# dual-verter.net
KiCad netlist of a schematic drawn in EAGLE
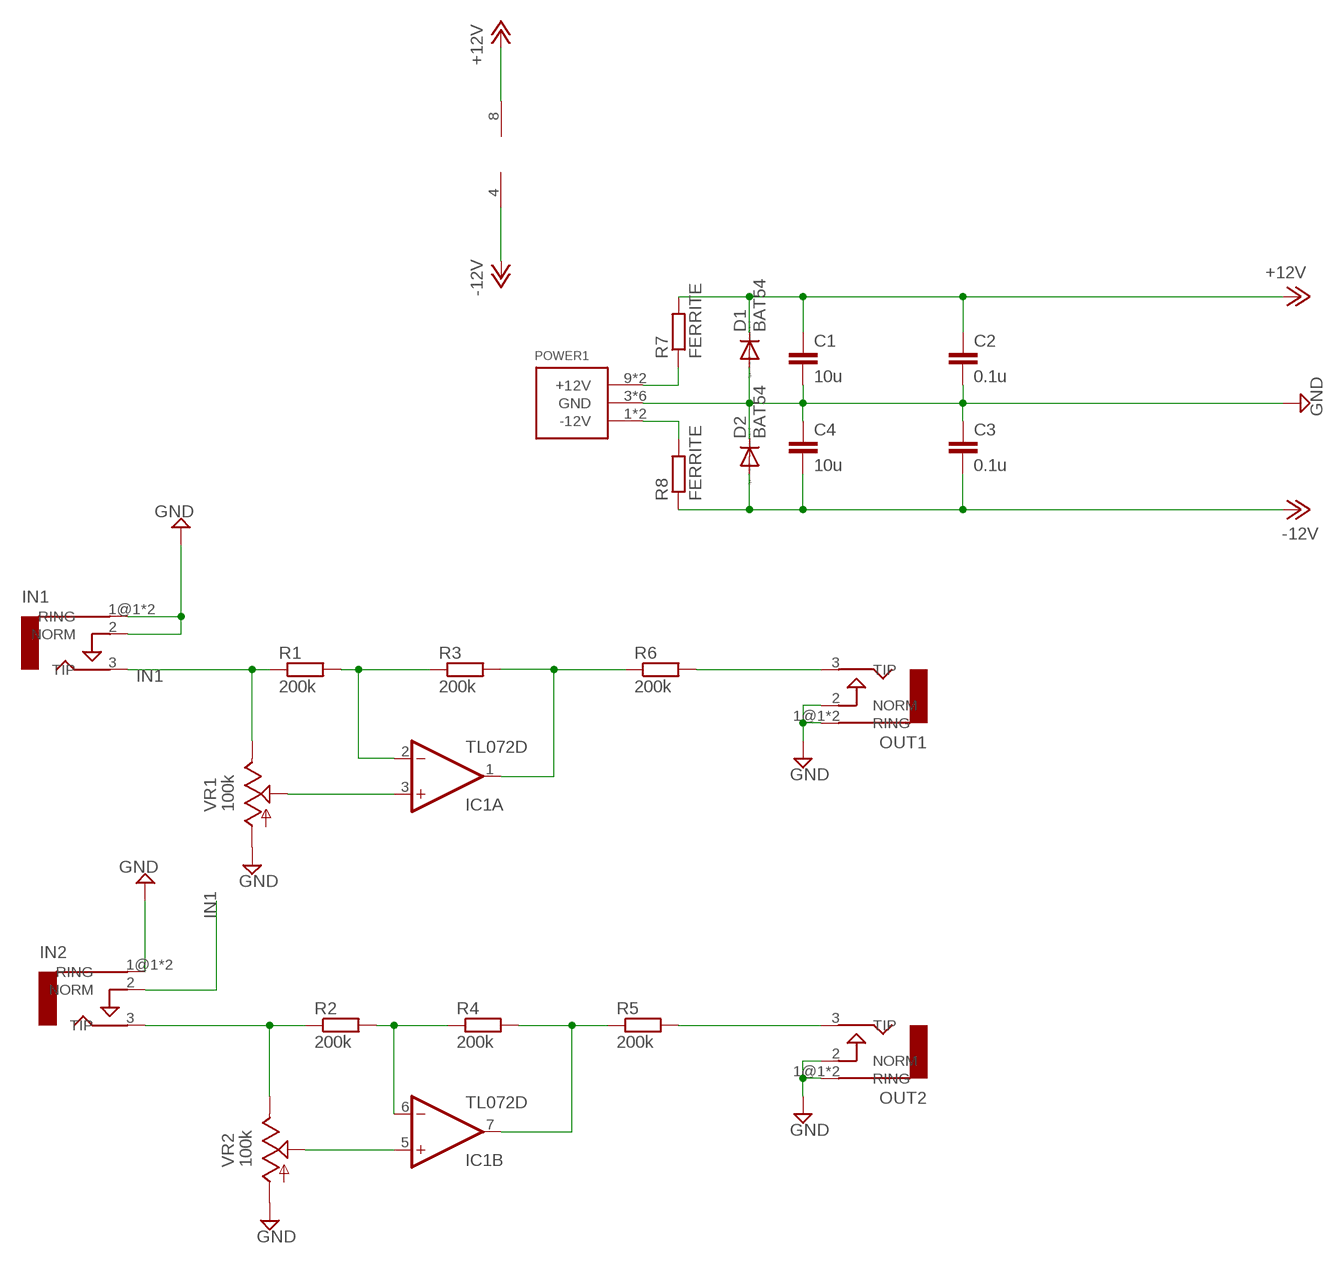
[diagram p0: schematic, sheet 1]

(export (version "E")
  (design (tool "Eeschema 10.0.6"))
  (components
    (comp (ref "C1")
      (value "10u")
      (footprint "eagle-import:C0805")
      (libsource (lib "eagle-import") (part "C-EUC0805"))
    )
    (comp (ref "C2")
      (value "0.1u")
      (footprint "eagle-import:C0805")
      (libsource (lib "eagle-import") (part "C-EUC0805"))
    )
    (comp (ref "C3")
      (value "0.1u")
      (footprint "eagle-import:C0805")
      (libsource (lib "eagle-import") (part "C-EUC0805"))
    )
    (comp (ref "C4")
      (value "10u")
      (footprint "eagle-import:C0805")
      (libsource (lib "eagle-import") (part "C-EUC0805"))
    )
    (comp (ref "D1")
      (value "BAT54")
      (footprint "eagle-import:SOD323-W")
      (libsource (lib "eagle-import") (part "DIODE-SOD323-W"))
    )
    (comp (ref "D2")
      (value "BAT54")
      (footprint "eagle-import:SOD323-W")
      (libsource (lib "eagle-import") (part "DIODE-SOD323-W"))
    )
    (comp (ref "IC1")
      (value "TL072D")
      (footprint "eagle-import:SO08")
      (libsource (lib "eagle-import") (part "TL072D"))
    )
    (comp (ref "IN1")
      (value "AUDIO-JACKERTHENVAR")
      (footprint "eagle-import:ERTHENVAR-JACK")
      (libsource (lib "eagle-import") (part "AUDIO-JACKERTHENVAR"))
    )
    (comp (ref "IN2")
      (value "AUDIO-JACKERTHENVAR")
      (footprint "eagle-import:ERTHENVAR-JACK")
      (libsource (lib "eagle-import") (part "AUDIO-JACKERTHENVAR"))
    )
    (comp (ref "OUT1")
      (value "AUDIO-JACKERTHENVAR")
      (footprint "eagle-import:ERTHENVAR-JACK")
      (libsource (lib "eagle-import") (part "AUDIO-JACKERTHENVAR"))
    )
    (comp (ref "OUT2")
      (value "AUDIO-JACKERTHENVAR")
      (footprint "eagle-import:ERTHENVAR-JACK")
      (libsource (lib "eagle-import") (part "AUDIO-JACKERTHENVAR"))
    )
    (comp (ref "POWER1")
      (value "POWER_SIMPLE10")
      (footprint "eagle-import:POWER_10")
      (libsource (lib "eagle-import") (part "POWER_SIMPLE10"))
    )
    (comp (ref "R1")
      (value "200k")
      (footprint "eagle-import:R0805")
      (libsource (lib "eagle-import") (part "R-EU_R0805"))
    )
    (comp (ref "R2")
      (value "200k")
      (footprint "eagle-import:R0805")
      (libsource (lib "eagle-import") (part "R-EU_R0805"))
    )
    (comp (ref "R3")
      (value "200k")
      (footprint "eagle-import:R0805")
      (libsource (lib "eagle-import") (part "R-EU_R0805"))
    )
    (comp (ref "R4")
      (value "200k")
      (footprint "eagle-import:R0805")
      (libsource (lib "eagle-import") (part "R-EU_R0805"))
    )
    (comp (ref "R5")
      (value "200k")
      (footprint "eagle-import:R0805")
      (libsource (lib "eagle-import") (part "R-EU_R0805"))
    )
    (comp (ref "R6")
      (value "200k")
      (footprint "eagle-import:R0805")
      (libsource (lib "eagle-import") (part "R-EU_R0805"))
    )
    (comp (ref "R7")
      (value "FERRITE")
      (footprint "eagle-import:R0805")
      (libsource (lib "eagle-import") (part "R-EU_R0805"))
    )
    (comp (ref "R8")
      (value "FERRITE")
      (footprint "eagle-import:R0805")
      (libsource (lib "eagle-import") (part "R-EU_R0805"))
    )
    (comp (ref "VR1")
      (value "100k")
      (footprint "eagle-import:9MM_SNAP-IN_POT")
      (libsource (lib "eagle-import") (part "9MM_SNAP-IN_POT_"))
    )
    (comp (ref "VR2")
      (value "100k")
      (footprint "eagle-import:9MM_SNAP-IN_POT")
      (libsource (lib "eagle-import") (part "9MM_SNAP-IN_POT_"))
    )
  )
  (nets
    (net (code "1") (name "+12V") (class "Default")
      (node (ref "C1") (pin "1") (pinfunction "1_1") (pintype "passive"))
      (node (ref "C2") (pin "1") (pinfunction "1_1") (pintype "passive"))
      (node (ref "D1") (pin "C") (pinfunction "C_C") (pintype "passive"))
      (node (ref "IC1") (pin "8") (pinfunction "V+_8") (pintype "power_in"))
      (node (ref "R7") (pin "2") (pinfunction "2_2") (pintype "passive"))
    )
    (net (code "2") (name "-12V") (class "Default")
      (node (ref "C3") (pin "2") (pinfunction "2_2") (pintype "passive"))
      (node (ref "C4") (pin "2") (pinfunction "2_2") (pintype "passive"))
      (node (ref "D2") (pin "A") (pinfunction "A_A") (pintype "passive"))
      (node (ref "IC1") (pin "4") (pinfunction "V-_4") (pintype "power_in"))
      (node (ref "R8") (pin "1") (pinfunction "1_1") (pintype "passive"))
    )
    (net (code "3") (name "/IN1") (class "Default")
      (node (ref "IN1") (pin "3") (pinfunction "TIP_3") (pintype "bidirectional"))
      (node (ref "IN2") (pin "2") (pinfunction "NORM_2") (pintype "bidirectional"))
      (node (ref "R1") (pin "1") (pinfunction "1_1") (pintype "passive"))
      (node (ref "VR1") (pin "3") (pinfunction "E_3") (pintype "passive"))
    )
    (net (code "4") (name "GND") (class "Default")
      (node (ref "C1") (pin "2") (pinfunction "2_2") (pintype "passive"))
      (node (ref "C2") (pin "2") (pinfunction "2_2") (pintype "passive"))
      (node (ref "C3") (pin "1") (pinfunction "1_1") (pintype "passive"))
      (node (ref "C4") (pin "1") (pinfunction "1_1") (pintype "passive"))
      (node (ref "D1") (pin "A") (pinfunction "A_A") (pintype "passive"))
      (node (ref "D2") (pin "C") (pinfunction "C_C") (pintype "passive"))
      (node (ref "IN1") (pin "1@1") (pinfunction "RING_1@1") (pintype "bidirectional"))
      (node (ref "IN1") (pin "1@2") (pinfunction "RING_1@2") (pintype "bidirectional"))
      (node (ref "IN1") (pin "2") (pinfunction "NORM_2") (pintype "bidirectional"))
      (node (ref "IN2") (pin "1@1") (pinfunction "RING_1@1") (pintype "bidirectional"))
      (node (ref "IN2") (pin "1@2") (pinfunction "RING_1@2") (pintype "bidirectional"))
      (node (ref "OUT1") (pin "1@1") (pinfunction "RING_1@1") (pintype "bidirectional"))
      (node (ref "OUT1") (pin "1@2") (pinfunction "RING_1@2") (pintype "bidirectional"))
      (node (ref "OUT1") (pin "2") (pinfunction "NORM_2") (pintype "bidirectional"))
      (node (ref "OUT2") (pin "1@1") (pinfunction "RING_1@1") (pintype "bidirectional"))
      (node (ref "OUT2") (pin "1@2") (pinfunction "RING_1@2") (pintype "bidirectional"))
      (node (ref "OUT2") (pin "2") (pinfunction "NORM_2") (pintype "bidirectional"))
      (node (ref "POWER1") (pin "3") (pinfunction "GND_3") (pintype "bidirectional"))
      (node (ref "POWER1") (pin "4") (pinfunction "GND_4") (pintype "bidirectional"))
      (node (ref "POWER1") (pin "5") (pinfunction "GND_5") (pintype "bidirectional"))
      (node (ref "POWER1") (pin "6") (pinfunction "GND_6") (pintype "bidirectional"))
      (node (ref "POWER1") (pin "7") (pinfunction "GND_7") (pintype "bidirectional"))
      (node (ref "POWER1") (pin "8") (pinfunction "GND_8") (pintype "bidirectional"))
      (node (ref "VR1") (pin "1") (pinfunction "A_1") (pintype "passive"))
      (node (ref "VR2") (pin "1") (pinfunction "A_1") (pintype "passive"))
    )
    (net (code "5") (name "Net-(IC1A-+IN)") (class "Default")
      (node (ref "IC1") (pin "3") (pinfunction "+IN_3") (pintype "input"))
      (node (ref "VR1") (pin "2") (pinfunction "S_2") (pintype "passive"))
    )
    (net (code "6") (name "Net-(IC1A--IN)") (class "Default")
      (node (ref "IC1") (pin "2") (pinfunction "-IN_2") (pintype "input"))
      (node (ref "R1") (pin "2") (pinfunction "2_2") (pintype "passive"))
      (node (ref "R3") (pin "1") (pinfunction "1_1") (pintype "passive"))
    )
    (net (code "7") (name "Net-(IC1A-OUT)") (class "Default")
      (node (ref "IC1") (pin "1") (pinfunction "OUT_1") (pintype "output"))
      (node (ref "R3") (pin "2") (pinfunction "2_2") (pintype "passive"))
      (node (ref "R6") (pin "1") (pinfunction "1_1") (pintype "passive"))
    )
    (net (code "8") (name "Net-(IC1B-+IN)") (class "Default")
      (node (ref "IC1") (pin "5") (pinfunction "+IN_5") (pintype "input"))
      (node (ref "VR2") (pin "2") (pinfunction "S_2") (pintype "passive"))
    )
    (net (code "9") (name "Net-(IC1B--IN)") (class "Default")
      (node (ref "IC1") (pin "6") (pinfunction "-IN_6") (pintype "input"))
      (node (ref "R2") (pin "2") (pinfunction "2_2") (pintype "passive"))
      (node (ref "R4") (pin "1") (pinfunction "1_1") (pintype "passive"))
    )
    (net (code "10") (name "Net-(IC1B-OUT)") (class "Default")
      (node (ref "IC1") (pin "7") (pinfunction "OUT_7") (pintype "output"))
      (node (ref "R4") (pin "2") (pinfunction "2_2") (pintype "passive"))
      (node (ref "R5") (pin "1") (pinfunction "1_1") (pintype "passive"))
    )
    (net (code "11") (name "Net-(IN2-TIP)") (class "Default")
      (node (ref "IN2") (pin "3") (pinfunction "TIP_3") (pintype "bidirectional"))
      (node (ref "R2") (pin "1") (pinfunction "1_1") (pintype "passive"))
      (node (ref "VR2") (pin "3") (pinfunction "E_3") (pintype "passive"))
    )
    (net (code "12") (name "Net-(OUT1-TIP)") (class "Default")
      (node (ref "OUT1") (pin "3") (pinfunction "TIP_3") (pintype "bidirectional"))
      (node (ref "R6") (pin "2") (pinfunction "2_2") (pintype "passive"))
    )
    (net (code "13") (name "Net-(OUT2-TIP)") (class "Default")
      (node (ref "OUT2") (pin "3") (pinfunction "TIP_3") (pintype "bidirectional"))
      (node (ref "R5") (pin "2") (pinfunction "2_2") (pintype "passive"))
    )
    (net (code "14") (name "Net-(POWER1-+12V-Pad10)") (class "Default")
      (node (ref "POWER1") (pin "10") (pinfunction "+12V_10") (pintype "bidirectional"))
      (node (ref "POWER1") (pin "9") (pinfunction "+12V_9") (pintype "bidirectional"))
      (node (ref "R7") (pin "1") (pinfunction "1_1") (pintype "passive"))
    )
    (net (code "15") (name "Net-(POWER1--12V-Pad1)") (class "Default")
      (node (ref "POWER1") (pin "1") (pinfunction "-12V_1") (pintype "bidirectional"))
      (node (ref "POWER1") (pin "2") (pinfunction "-12V_2") (pintype "bidirectional"))
      (node (ref "R8") (pin "2") (pinfunction "2_2") (pintype "passive"))
    )
  )
)
